# Sensors.net
KiCad netlist of a schematic drawn in Altium Designer
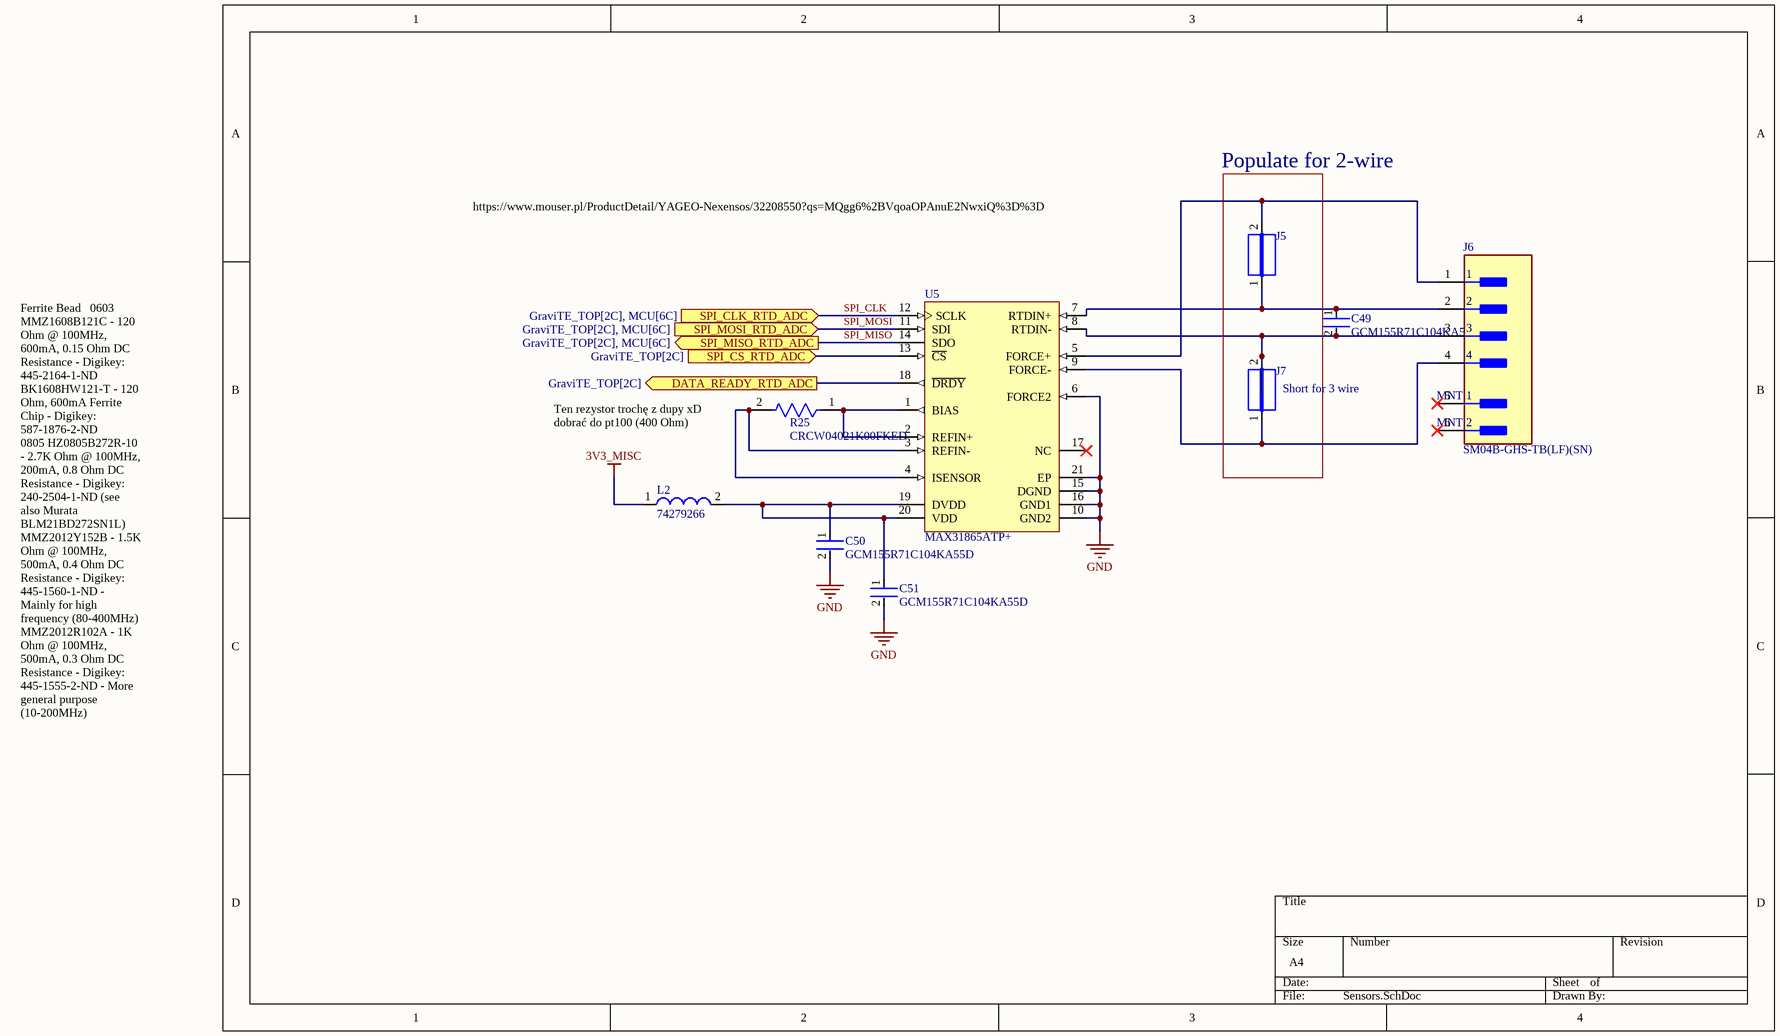
[diagram p0: Sensors.SchDoc]

(export (version "E")
  (design (tool "Eeschema 10.0.6"))
  (components
    (comp (ref "C49")
      (value "GCM155R71C104KA55D")
      (footprint "FP-GCM155-0_05-IPC_C")
      (description "Ceramic Capacitor for Automotive 100nF ±10% 16VDC X7R 0402 Paper T/R")
      (fields (field (name "VOLTAGE") "16V") (field (name "TOLERANCE") "10%"))
      (libsource (lib "Altium Content Vault") (part "02cd4be3c70576c341d710602a673aa"))
    )
    (comp (ref "C50")
      (value "GCM155R71C104KA55D")
      (footprint "FP-GCM155-0_05-IPC_C")
      (description "Ceramic Capacitor for Automotive 100nF ±10% 16VDC X7R 0402 Paper T/R")
      (fields (field (name "VOLTAGE") "16V") (field (name "TOLERANCE") "10%"))
      (libsource (lib "Altium Content Vault") (part "02cd4be3c70576c341d710602a673aa"))
    )
    (comp (ref "C51")
      (value "GCM155R71C104KA55D")
      (footprint "FP-GCM155-0_05-IPC_C")
      (description "Ceramic Capacitor for Automotive 100nF ±10% 16VDC X7R 0402 Paper T/R")
      (fields (field (name "VOLTAGE") "16V") (field (name "TOLERANCE") "10%"))
      (libsource (lib "Altium Content Vault") (part "02cd4be3c70576c341d710602a673aa"))
    )
    (comp (ref "J5")
      (value "JUMPER")
      (footprint "JUMPER")
      (libsource (lib "Piotr Słonka - priv") (part "JUMPER"))
    )
    (comp (ref "J6")
      (value "SM04B-GHS-TB(LF)(SN)")
      (footprint "FP-SM04B-GHS-TB_LF_SN-MFG")
      (description "CONN HEADER SMD R/A 4POS 1.25MM")
      (libsource (lib "Altium Content Vault") (part "f4320a1371cd6270e33bce1916c33c0"))
    )
    (comp (ref "J7")
      (value "JUMPER")
      (footprint "JUMPER")
      (libsource (lib "Piotr Słonka - priv") (part "JUMPER"))
    )
    (comp (ref "L2")
      (value "74279266")
      (footprint "SMD-0603")
      (description "SMD EMI Suppression Ferrite Bead WE-CBF, Z = 1000 Ohm")
      (libsource (lib "Altium Content Vault") (part "PAS-IND-INDUCTOR-2"))
    )
    (comp (ref "R25")
      (value "CRCW04021K00FKED")
      (footprint "FP-CRCW0402-e3-MFG")
      (description "RES Thick Film, 1kΩ, 1%, 0.063W, 100ppm/°C, 0402")
      (fields (field (name "TOLERANCE") "1%"))
      (libsource (lib "Altium Content Vault") (part "1029c3af85768c4190bb7ad29bc67b5"))
    )
    (comp (ref "U5")
      (value "MAX31865ATP+")
      (footprint "MAXM-T2055+5_L")
      (fields (field (name "GENERIC PART NUMBER") "MAX31865"))
      (libsource (lib "Altium Content Vault") (part "MAX31865-T2055+5"))
    )
  )
  (nets
    (net (code "1") (name "/DATA_READY_RTD_ADC") (class "Default")
      (node (ref "U5") (pin "18") (pinfunction "~{DRDY}_18") (pintype "output"))
    )
    (net (code "2") (name "/SPI_CLK") (class "Default")
      (node (ref "U5") (pin "12") (pinfunction "SCLK_12") (pintype "input"))
    )
    (net (code "3") (name "/SPI_CS_RTD_ADC") (class "Default")
      (node (ref "U5") (pin "13") (pinfunction "~{CS}_13") (pintype "input"))
    )
    (net (code "4") (name "/SPI_MISO") (class "Default")
      (node (ref "U5") (pin "14") (pinfunction "SDO_14") (pintype "tri_state"))
    )
    (net (code "5") (name "/SPI_MOSI") (class "Default")
      (node (ref "U5") (pin "11") (pinfunction "SDI_11") (pintype "input"))
    )
    (net (code "6") (name "3V3_MISC") (class "Default")
      (node (ref "L2") (pin "1") (pinfunction "1_1") (pintype "passive"))
    )
    (net (code "7") (name "GND") (class "Default")
      (node (ref "C50") (pin "2") (pinfunction "2_2") (pintype "passive"))
      (node (ref "C51") (pin "2") (pinfunction "2_2") (pintype "passive"))
      (node (ref "U5") (pin "10") (pinfunction "GND2_10") (pintype "power_in"))
      (node (ref "U5") (pin "15") (pinfunction "DGND_15") (pintype "power_in"))
      (node (ref "U5") (pin "16") (pinfunction "GND1_16") (pintype "power_in"))
      (node (ref "U5") (pin "21") (pinfunction "EP_21") (pintype "power_in"))
      (node (ref "U5") (pin "6") (pinfunction "FORCE2_6") (pintype "input"))
    )
    (net (code "8") (name "Net-(U5-BIAS)") (class "Default")
      (node (ref "R25") (pin "1") (pinfunction "1_1") (pintype "passive"))
      (node (ref "U5") (pin "1") (pinfunction "BIAS_1") (pintype "output"))
      (node (ref "U5") (pin "2") (pinfunction "REFIN+_2") (pintype "input"))
    )
    (net (code "9") (name "Net-(U5-DVDD)") (class "Default")
      (node (ref "C50") (pin "1") (pinfunction "1_1") (pintype "passive"))
      (node (ref "C51") (pin "1") (pinfunction "1_1") (pintype "passive"))
      (node (ref "L2") (pin "2") (pinfunction "2_2") (pintype "passive"))
      (node (ref "U5") (pin "19") (pinfunction "DVDD_19") (pintype "power_in"))
      (node (ref "U5") (pin "20") (pinfunction "VDD_20") (pintype "power_in"))
    )
    (net (code "10") (name "Net-(U5-FORCE+)") (class "Default")
      (node (ref "J5") (pin "2") (pinfunction "2_2") (pintype "passive"))
      (node (ref "J6") (pin "1") (pinfunction "1_1") (pintype "passive"))
      (node (ref "U5") (pin "5") (pinfunction "FORCE+_5") (pintype "input"))
    )
    (net (code "11") (name "Net-(U5-FORCE-)") (class "Default")
      (node (ref "J6") (pin "4") (pinfunction "4_4") (pintype "passive"))
      (node (ref "J7") (pin "1") (pinfunction "1_1") (pintype "passive"))
      (node (ref "U5") (pin "9") (pinfunction "FORCE-_9") (pintype "input"))
    )
    (net (code "12") (name "Net-(U5-ISENSOR)") (class "Default")
      (node (ref "R25") (pin "2") (pinfunction "2_2") (pintype "passive"))
      (node (ref "U5") (pin "3") (pinfunction "REFIN-_3") (pintype "input"))
      (node (ref "U5") (pin "4") (pinfunction "ISENSOR_4") (pintype "input"))
    )
    (net (code "13") (name "Net-(U5-RTDIN+)") (class "Default")
      (node (ref "C49") (pin "1") (pinfunction "1_1") (pintype "passive"))
      (node (ref "J5") (pin "1") (pinfunction "1_1") (pintype "passive"))
      (node (ref "J6") (pin "2") (pinfunction "2_2") (pintype "passive"))
      (node (ref "U5") (pin "7") (pinfunction "RTDIN+_7") (pintype "input"))
    )
    (net (code "14") (name "Net-(U5-RTDIN-)") (class "Default")
      (node (ref "C49") (pin "2") (pinfunction "2_2") (pintype "passive"))
      (node (ref "J6") (pin "3") (pinfunction "3_3") (pintype "passive"))
      (node (ref "J7") (pin "2") (pinfunction "2_2") (pintype "passive"))
      (node (ref "U5") (pin "8") (pinfunction "RTDIN-_8") (pintype "input"))
    )
    (net (code "15") (name "unconnected-(J6-MNT_1-Pad5)") (class "Default")
      (node (ref "J6") (pin "5") (pinfunction "MNT_1_5") (pintype "passive+no_connect"))
    )
    (net (code "16") (name "unconnected-(J6-MNT_2-Pad6)") (class "Default")
      (node (ref "J6") (pin "6") (pinfunction "MNT_2_6") (pintype "passive+no_connect"))
    )
    (net (code "17") (name "unconnected-(U5-NC-Pad17)") (class "Default")
      (node (ref "U5") (pin "17") (pinfunction "NC_17") (pintype "passive+no_connect"))
    )
  )
)
